# Radar_Connector.net
KiCad netlist of a schematic drawn in Altium Designer
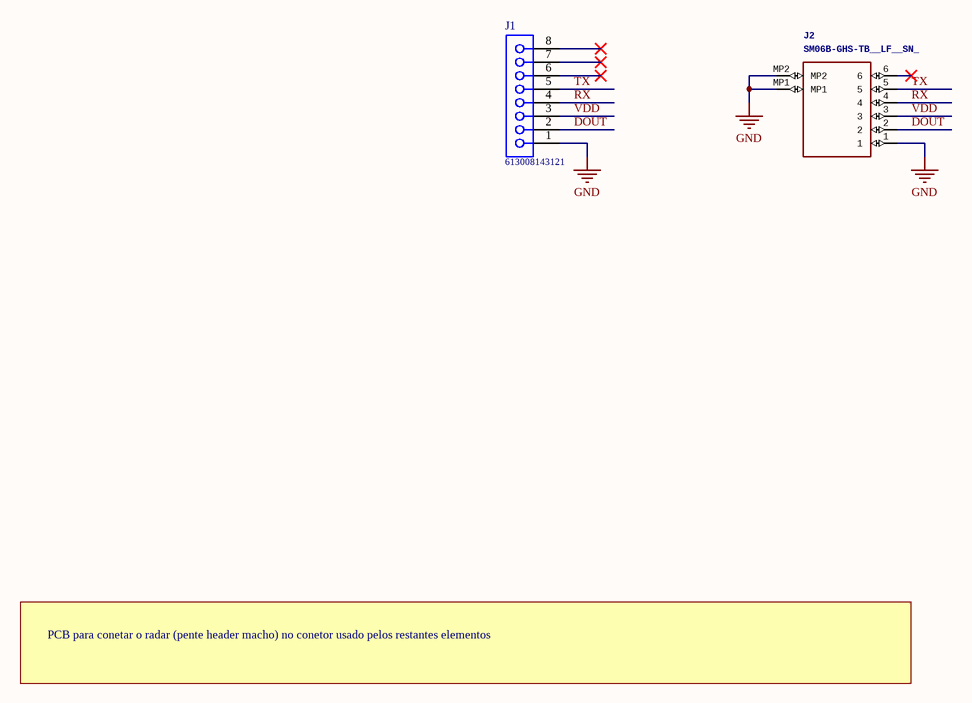
[diagram p0: Radar_Connector.SchDoc]

(export (version "E")
  (design (tool "Eeschema 10.0.6"))
  (components
    (comp (ref "J1")
      (value "613008143121")
      (footprint "613008143121")
      (description "WR-PHD Socket Header, THT, pitch 2.54mm, Single Row, Angled, 8pin")
      (fields (field (name "PUBLISHER") "Wurth Elektronik"))
      (libsource (lib "WR-PHD Headers") (part "613008143121"))
    )
    (comp (ref "J2")
      (value "SM06B-GHS-TB__LF__SN_")
      (footprint "SM06BGHSTBLFSN")
      (description "Conn Shrouded Header HDR 6 POS 1.25mm Solder RA Side Entry SMD T/R   Source:  Datasheet")
      (fields (field (name "MANUFACTURER_PART_NUMBER") "SM06B-GHS-TB (LF)(SN)"))
      (libsource (lib "FDS") (part "SM06B-GHS-TB__LF__SN_"))
    )
  )
  (nets
    (net (code "1") (name "/DOUT") (class "Default")
      (node (ref "J1") (pin "2") (pinfunction "2_2") (pintype "passive"))
      (node (ref "J2") (pin "2") (pinfunction "2_2") (pintype "bidirectional"))
    )
    (net (code "2") (name "/RX") (class "Default")
      (node (ref "J1") (pin "4") (pinfunction "4_4") (pintype "passive"))
      (node (ref "J2") (pin "4") (pinfunction "4_4") (pintype "bidirectional"))
    )
    (net (code "3") (name "/TX") (class "Default")
      (node (ref "J1") (pin "5") (pinfunction "5_5") (pintype "passive"))
      (node (ref "J2") (pin "5") (pinfunction "5_5") (pintype "bidirectional"))
    )
    (net (code "4") (name "/VDD") (class "Default")
      (node (ref "J1") (pin "3") (pinfunction "3_3") (pintype "passive"))
      (node (ref "J2") (pin "3") (pinfunction "3_3") (pintype "bidirectional"))
    )
    (net (code "5") (name "GND") (class "Default")
      (node (ref "J1") (pin "1") (pinfunction "1_1") (pintype "passive"))
      (node (ref "J2") (pin "1") (pinfunction "1_1") (pintype "bidirectional"))
      (node (ref "J2") (pin "MP1") (pinfunction "MP1_MP1") (pintype "bidirectional"))
      (node (ref "J2") (pin "MP2") (pinfunction "MP2_MP2") (pintype "bidirectional"))
    )
    (net (code "6") (name "unconnected-(J1-Pad6)") (class "Default")
      (node (ref "J1") (pin "6") (pinfunction "6_6") (pintype "passive+no_connect"))
    )
    (net (code "7") (name "unconnected-(J1-Pad7)") (class "Default")
      (node (ref "J1") (pin "7") (pinfunction "7_7") (pintype "passive+no_connect"))
    )
    (net (code "8") (name "unconnected-(J1-Pad8)") (class "Default")
      (node (ref "J1") (pin "8") (pinfunction "8_8") (pintype "passive+no_connect"))
    )
    (net (code "9") (name "unconnected-(J2-Pad6)") (class "Default")
      (node (ref "J2") (pin "6") (pinfunction "6_6") (pintype "bidirectional+no_connect"))
    )
  )
)
